# MCX-A153__Shield_Template.net
KiCad netlist of a schematic drawn in Altium Designer
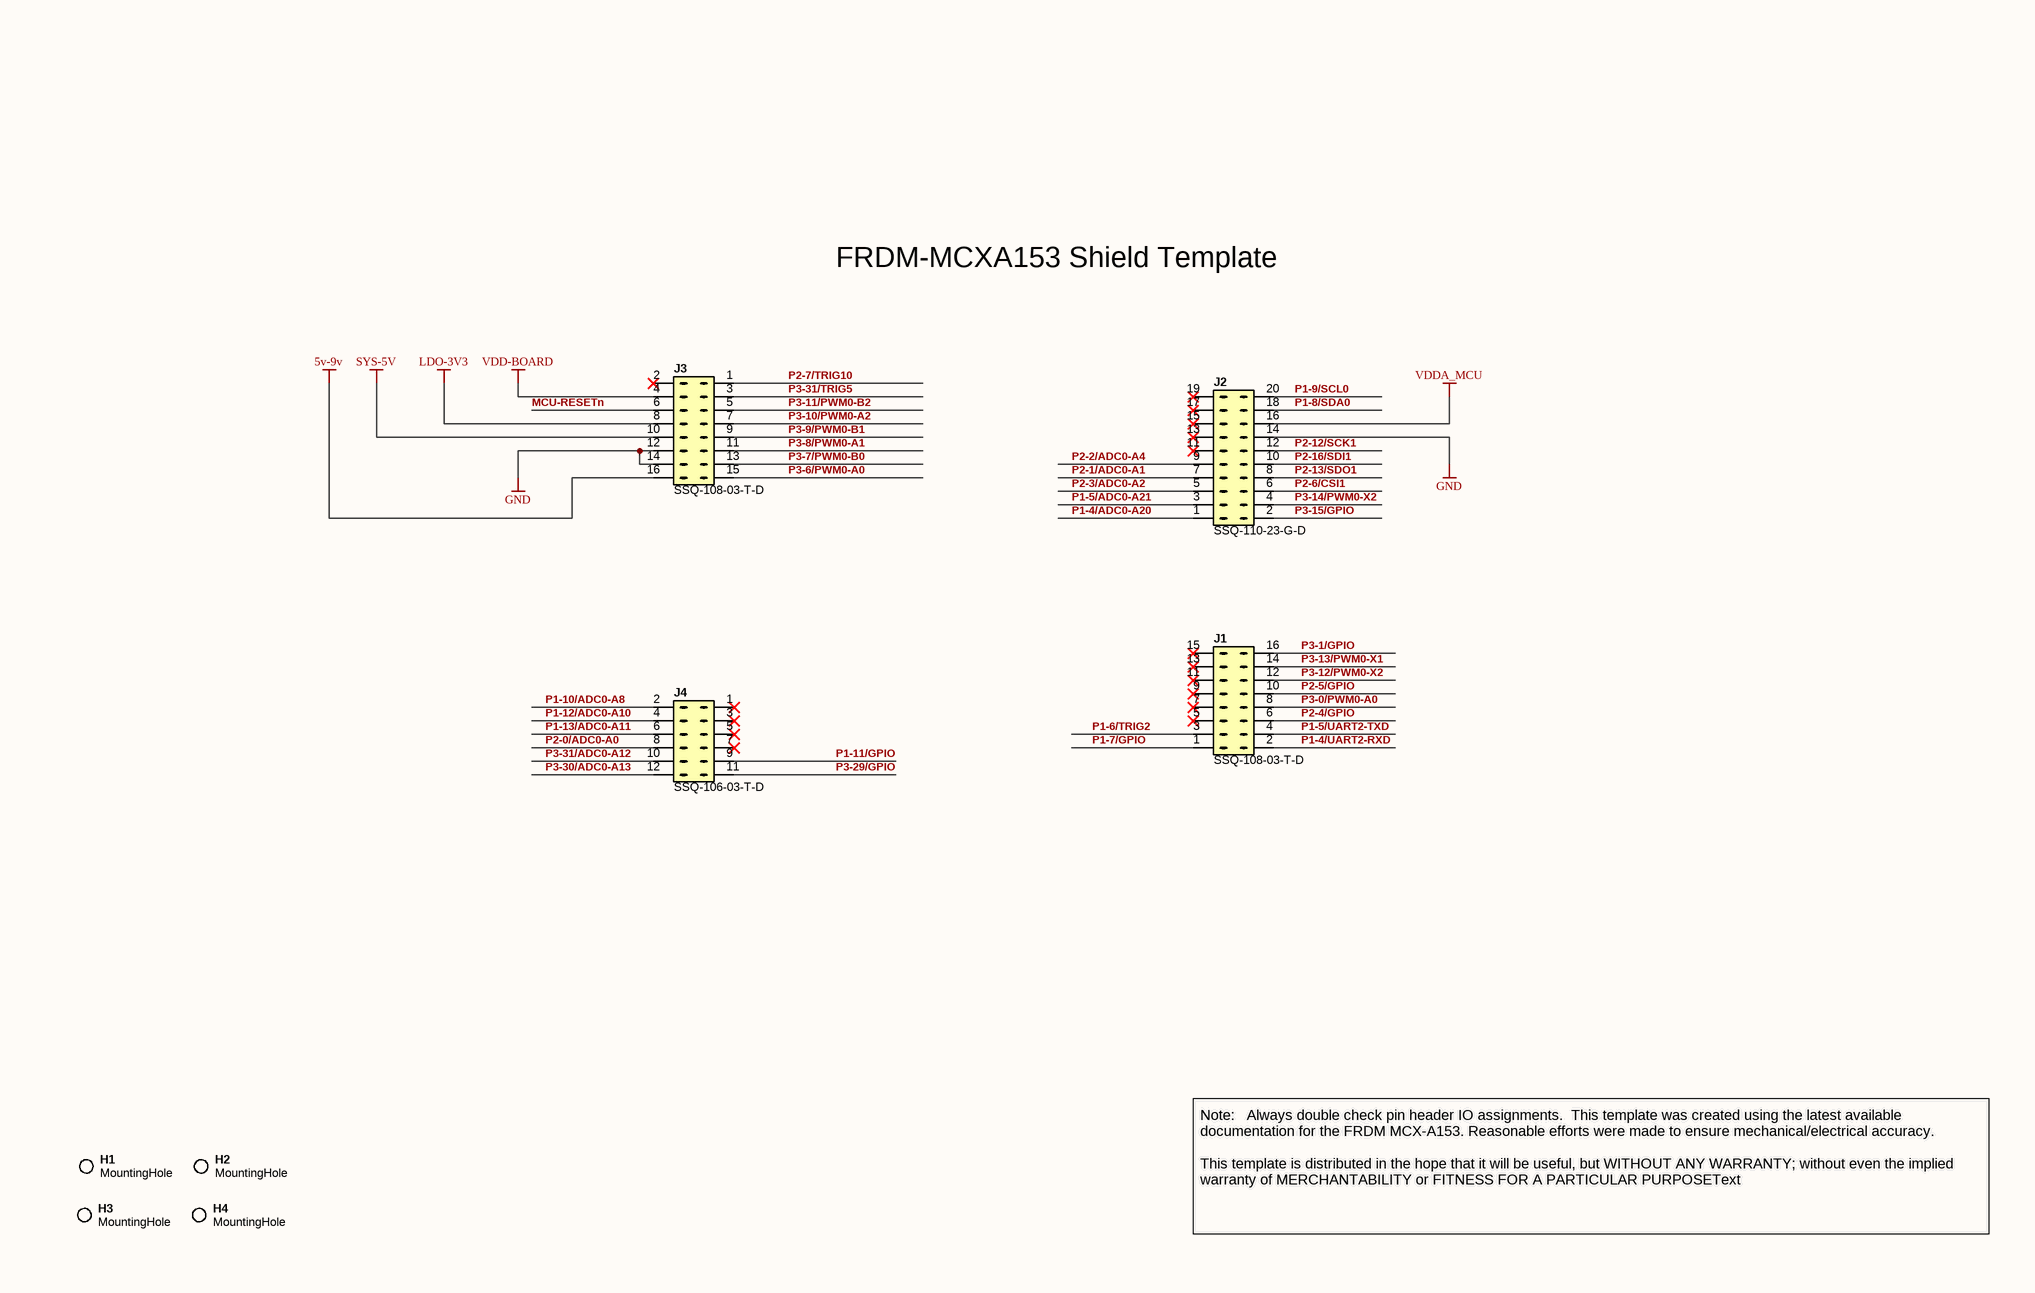
[diagram p0: MCX-A153__Shield_Template.SchDoc]

(export (version "E")
  (design (tool "Eeschema 10.0.6"))
  (components
    (comp (ref "H1")
      (value "MountingHole")
      (footprint "MountingHole_3.2mm_M3")
      (fields (field (name "Comment") "Mechanical_MountingHole"))
      (libsource (lib "altium-import") (part "root_0_Mechanical_MountingHole_"))
    )
    (comp (ref "H2")
      (value "MountingHole")
      (footprint "MountingHole_3.2mm_M3")
      (fields (field (name "Comment") "Mechanical_MountingHole"))
      (libsource (lib "altium-import") (part "root_0_Mechanical_MountingHole_"))
    )
    (comp (ref "H3")
      (value "MountingHole")
      (footprint "MountingHole_3.2mm_M3")
      (fields (field (name "Comment") "Mechanical_MountingHole"))
      (libsource (lib "altium-import") (part "root_0_Mechanical_MountingHole_"))
    )
    (comp (ref "H4")
      (value "MountingHole")
      (footprint "MountingHole_3.2mm_M3")
      (fields (field (name "Comment") "Mechanical_MountingHole"))
      (libsource (lib "altium-import") (part "root_0_Mechanical_MountingHole_"))
    )
    (comp (ref "J1")
      (value "SSQ-108-03-T-D")
      (footprint "SSQ-108-03-T-D")
      (fields
        (field (name "MANUFACTURER") "Samtec Inc.")
        (field (name "MANUFACTURER PART NUMBER") "SSQ-110-23-G-D")
      )
      (libsource (lib "MCX-A153_Shield_Template") (part "Connector_Generic_Conn_02x08_Odd_Even"))
    )
    (comp (ref "J2")
      (value "SSQ-110-23-G-D")
      (footprint "SSQ-110-23-G-D")
      (fields (field (name "MANUFACTURER") "Samtec Inc."))
      (libsource (lib "MCX-A153_Shield_Template") (part "Connector_Generic_Conn_02x10_Odd_Even"))
    )
    (comp (ref "J3")
      (value "SSQ-108-03-T-D")
      (footprint "SSQ-108-03-T-D")
      (fields
        (field (name "MANUFACTURER") "Samtec Inc.")
        (field (name "MANUFACTURER PART NUMBER") "SSQ-110-23-G-D")
      )
      (libsource (lib "") (part "Connector_Generic_Conn_02x08_Odd_Even_1"))
    )
    (comp (ref "J4")
      (value "SSQ-106-03-T-D")
      (footprint "SSQ-106-03-T-D")
      (fields (field (name "MANUFACTURER") "Samtec Inc."))
      (libsource (lib "MCX-A153_Shield_Template") (part "Connector_Generic_Conn_02x06_Odd_Even"))
    )
  )
  (nets
    (net (code "1") (name "/MCU-RESETn") (class "Default")
      (node (ref "J3") (pin "6") (pinfunction "Pin_6_6") (pintype "passive"))
    )
    (net (code "2") (name "/P1-4{slash}ADC0-A20") (class "Default")
      (node (ref "J2") (pin "1") (pinfunction "Pin_1_1") (pintype "passive"))
    )
    (net (code "3") (name "/P1-4{slash}UART2-RXD") (class "Default")
      (node (ref "J1") (pin "2") (pinfunction "Pin_2_2") (pintype "passive"))
    )
    (net (code "4") (name "/P1-5{slash}ADC0-A21") (class "Default")
      (node (ref "J2") (pin "3") (pinfunction "Pin_3_3") (pintype "passive"))
    )
    (net (code "5") (name "/P1-5{slash}UART2-TXD") (class "Default")
      (node (ref "J1") (pin "4") (pinfunction "Pin_4_4") (pintype "passive"))
    )
    (net (code "6") (name "/P1-6{slash}TRIG2") (class "Default")
      (node (ref "J1") (pin "3") (pinfunction "Pin_3_3") (pintype "passive"))
    )
    (net (code "7") (name "/P1-7{slash}GPIO") (class "Default")
      (node (ref "J1") (pin "1") (pinfunction "Pin_1_1") (pintype "passive"))
    )
    (net (code "8") (name "/P1-8{slash}SDA0") (class "Default")
      (node (ref "J2") (pin "18") (pinfunction "Pin_18_18") (pintype "passive"))
    )
    (net (code "9") (name "/P1-9{slash}SCL0") (class "Default")
      (node (ref "J2") (pin "20") (pinfunction "Pin_20_20") (pintype "passive"))
    )
    (net (code "10") (name "/P1-10{slash}ADC0-A8") (class "Default")
      (node (ref "J4") (pin "2") (pinfunction "Pin_2_2") (pintype "passive"))
    )
    (net (code "11") (name "/P1-11{slash}GPIO") (class "Default")
      (node (ref "J4") (pin "9") (pinfunction "Pin_9_9") (pintype "passive"))
    )
    (net (code "12") (name "/P1-12{slash}ADC0-A10") (class "Default")
      (node (ref "J4") (pin "4") (pinfunction "Pin_4_4") (pintype "passive"))
    )
    (net (code "13") (name "/P1-13{slash}ADC0-A11") (class "Default")
      (node (ref "J4") (pin "6") (pinfunction "Pin_6_6") (pintype "passive"))
    )
    (net (code "14") (name "/P2-0{slash}ADC0-A0") (class "Default")
      (node (ref "J4") (pin "8") (pinfunction "Pin_8_8") (pintype "passive"))
    )
    (net (code "15") (name "/P2-1{slash}ADC0-A1") (class "Default")
      (node (ref "J2") (pin "7") (pinfunction "Pin_7_7") (pintype "passive"))
    )
    (net (code "16") (name "/P2-2{slash}ADC0-A4") (class "Default")
      (node (ref "J2") (pin "9") (pinfunction "Pin_9_9") (pintype "passive"))
    )
    (net (code "17") (name "/P2-3{slash}ADC0-A2") (class "Default")
      (node (ref "J2") (pin "5") (pinfunction "Pin_5_5") (pintype "passive"))
    )
    (net (code "18") (name "/P2-4{slash}GPIO") (class "Default")
      (node (ref "J1") (pin "6") (pinfunction "Pin_6_6") (pintype "passive"))
    )
    (net (code "19") (name "/P2-5{slash}GPIO") (class "Default")
      (node (ref "J1") (pin "10") (pinfunction "Pin_10_10") (pintype "passive"))
    )
    (net (code "20") (name "/P2-6{slash}CSI1") (class "Default")
      (node (ref "J2") (pin "6") (pinfunction "Pin_6_6") (pintype "passive"))
    )
    (net (code "21") (name "/P2-7{slash}TRIG10") (class "Default")
      (node (ref "J3") (pin "1") (pinfunction "Pin_1_1") (pintype "passive"))
    )
    (net (code "22") (name "/P2-12{slash}SCK1") (class "Default")
      (node (ref "J2") (pin "12") (pinfunction "Pin_12_12") (pintype "passive"))
    )
    (net (code "23") (name "/P2-13{slash}SDO1") (class "Default")
      (node (ref "J2") (pin "8") (pinfunction "Pin_8_8") (pintype "passive"))
    )
    (net (code "24") (name "/P2-16{slash}SDI1") (class "Default")
      (node (ref "J2") (pin "10") (pinfunction "Pin_10_10") (pintype "passive"))
    )
    (net (code "25") (name "/P3-0{slash}PWM0-A0") (class "Default")
      (node (ref "J1") (pin "8") (pinfunction "Pin_8_8") (pintype "passive"))
    )
    (net (code "26") (name "/P3-1{slash}GPIO") (class "Default")
      (node (ref "J1") (pin "16") (pinfunction "Pin_16_16") (pintype "passive"))
    )
    (net (code "27") (name "/P3-6{slash}PWM0-A0") (class "Default")
      (node (ref "J3") (pin "15") (pinfunction "Pin_15_15") (pintype "passive"))
    )
    (net (code "28") (name "/P3-7{slash}PWM0-B0") (class "Default")
      (node (ref "J3") (pin "13") (pinfunction "Pin_13_13") (pintype "passive"))
    )
    (net (code "29") (name "/P3-8{slash}PWM0-A1") (class "Default")
      (node (ref "J3") (pin "11") (pinfunction "Pin_11_11") (pintype "passive"))
    )
    (net (code "30") (name "/P3-9{slash}PWM0-B1") (class "Default")
      (node (ref "J3") (pin "9") (pinfunction "Pin_9_9") (pintype "passive"))
    )
    (net (code "31") (name "/P3-10{slash}PWM0-A2") (class "Default")
      (node (ref "J3") (pin "7") (pinfunction "Pin_7_7") (pintype "passive"))
    )
    (net (code "32") (name "/P3-11{slash}PWM0-B2") (class "Default")
      (node (ref "J3") (pin "5") (pinfunction "Pin_5_5") (pintype "passive"))
    )
    (net (code "33") (name "/P3-12{slash}PWM0-X2") (class "Default")
      (node (ref "J1") (pin "12") (pinfunction "Pin_12_12") (pintype "passive"))
    )
    (net (code "34") (name "/P3-13{slash}PWM0-X1") (class "Default")
      (node (ref "J1") (pin "14") (pinfunction "Pin_14_14") (pintype "passive"))
    )
    (net (code "35") (name "/P3-14{slash}PWM0-X2") (class "Default")
      (node (ref "J2") (pin "4") (pinfunction "Pin_4_4") (pintype "passive"))
    )
    (net (code "36") (name "/P3-15{slash}GPIO") (class "Default")
      (node (ref "J2") (pin "2") (pinfunction "Pin_2_2") (pintype "passive"))
    )
    (net (code "37") (name "/P3-29{slash}GPIO") (class "Default")
      (node (ref "J4") (pin "11") (pinfunction "Pin_11_11") (pintype "passive"))
    )
    (net (code "38") (name "/P3-30{slash}ADC0-A13") (class "Default")
      (node (ref "J4") (pin "12") (pinfunction "Pin_12_12") (pintype "passive"))
    )
    (net (code "39") (name "/P3-31{slash}ADC0-A12") (class "Default")
      (node (ref "J4") (pin "10") (pinfunction "Pin_10_10") (pintype "passive"))
    )
    (net (code "40") (name "/P3-31{slash}TRIG5") (class "Default")
      (node (ref "J3") (pin "3") (pinfunction "Pin_3_3") (pintype "passive"))
    )
    (net (code "41") (name "5v-9v") (class "Default")
      (node (ref "J3") (pin "16") (pinfunction "Pin_16_16") (pintype "passive"))
    )
    (net (code "42") (name "GND") (class "Default")
      (node (ref "J2") (pin "14") (pinfunction "Pin_14_14") (pintype "passive"))
      (node (ref "J3") (pin "12") (pinfunction "Pin_12_12") (pintype "passive"))
      (node (ref "J3") (pin "14") (pinfunction "Pin_14_14") (pintype "passive"))
    )
    (net (code "43") (name "LDO-3V3") (class "Default")
      (node (ref "J3") (pin "8") (pinfunction "Pin_8_8") (pintype "passive"))
    )
    (net (code "44") (name "SYS-5V") (class "Default")
      (node (ref "J3") (pin "10") (pinfunction "Pin_10_10") (pintype "passive"))
    )
    (net (code "45") (name "VDD-BOARD") (class "Default")
      (node (ref "J3") (pin "4") (pinfunction "Pin_4_4") (pintype "passive"))
    )
    (net (code "46") (name "VDDA_MCU") (class "Default")
      (node (ref "J2") (pin "16") (pinfunction "Pin_16_16") (pintype "passive"))
    )
    (net (code "47") (name "unconnected-(J1-Pin_5-Pad5)") (class "Default")
      (node (ref "J1") (pin "5") (pinfunction "Pin_5_5") (pintype "passive+no_connect"))
    )
    (net (code "48") (name "unconnected-(J1-Pin_7-Pad7)") (class "Default")
      (node (ref "J1") (pin "7") (pinfunction "Pin_7_7") (pintype "passive+no_connect"))
    )
    (net (code "49") (name "unconnected-(J1-Pin_9-Pad9)") (class "Default")
      (node (ref "J1") (pin "9") (pinfunction "Pin_9_9") (pintype "passive+no_connect"))
    )
    (net (code "50") (name "unconnected-(J1-Pin_11-Pad11)") (class "Default")
      (node (ref "J1") (pin "11") (pinfunction "Pin_11_11") (pintype "passive+no_connect"))
    )
    (net (code "51") (name "unconnected-(J1-Pin_13-Pad13)") (class "Default")
      (node (ref "J1") (pin "13") (pinfunction "Pin_13_13") (pintype "passive+no_connect"))
    )
    (net (code "52") (name "unconnected-(J1-Pin_15-Pad15)") (class "Default")
      (node (ref "J1") (pin "15") (pinfunction "Pin_15_15") (pintype "passive+no_connect"))
    )
    (net (code "53") (name "unconnected-(J2-Pin_11-Pad11)") (class "Default")
      (node (ref "J2") (pin "11") (pinfunction "Pin_11_11") (pintype "passive+no_connect"))
    )
    (net (code "54") (name "unconnected-(J2-Pin_13-Pad13)") (class "Default")
      (node (ref "J2") (pin "13") (pinfunction "Pin_13_13") (pintype "passive+no_connect"))
    )
    (net (code "55") (name "unconnected-(J2-Pin_15-Pad15)") (class "Default")
      (node (ref "J2") (pin "15") (pinfunction "Pin_15_15") (pintype "passive+no_connect"))
    )
    (net (code "56") (name "unconnected-(J2-Pin_17-Pad17)") (class "Default")
      (node (ref "J2") (pin "17") (pinfunction "Pin_17_17") (pintype "passive+no_connect"))
    )
    (net (code "57") (name "unconnected-(J2-Pin_19-Pad19)") (class "Default")
      (node (ref "J2") (pin "19") (pinfunction "Pin_19_19") (pintype "passive+no_connect"))
    )
    (net (code "58") (name "unconnected-(J3-Pin_2-Pad2)") (class "Default")
      (node (ref "J3") (pin "2") (pinfunction "Pin_2_2") (pintype "passive+no_connect"))
    )
    (net (code "59") (name "unconnected-(J4-Pin_1-Pad1)") (class "Default")
      (node (ref "J4") (pin "1") (pinfunction "Pin_1_1") (pintype "passive+no_connect"))
    )
    (net (code "60") (name "unconnected-(J4-Pin_3-Pad3)") (class "Default")
      (node (ref "J4") (pin "3") (pinfunction "Pin_3_3") (pintype "passive+no_connect"))
    )
    (net (code "61") (name "unconnected-(J4-Pin_5-Pad5)") (class "Default")
      (node (ref "J4") (pin "5") (pinfunction "Pin_5_5") (pintype "passive+no_connect"))
    )
    (net (code "62") (name "unconnected-(J4-Pin_7-Pad7)") (class "Default")
      (node (ref "J4") (pin "7") (pinfunction "Pin_7_7") (pintype "passive+no_connect"))
    )
  )
)
